# LoraPic2.net
KiCad netlist of a schematic drawn in Altium Designer
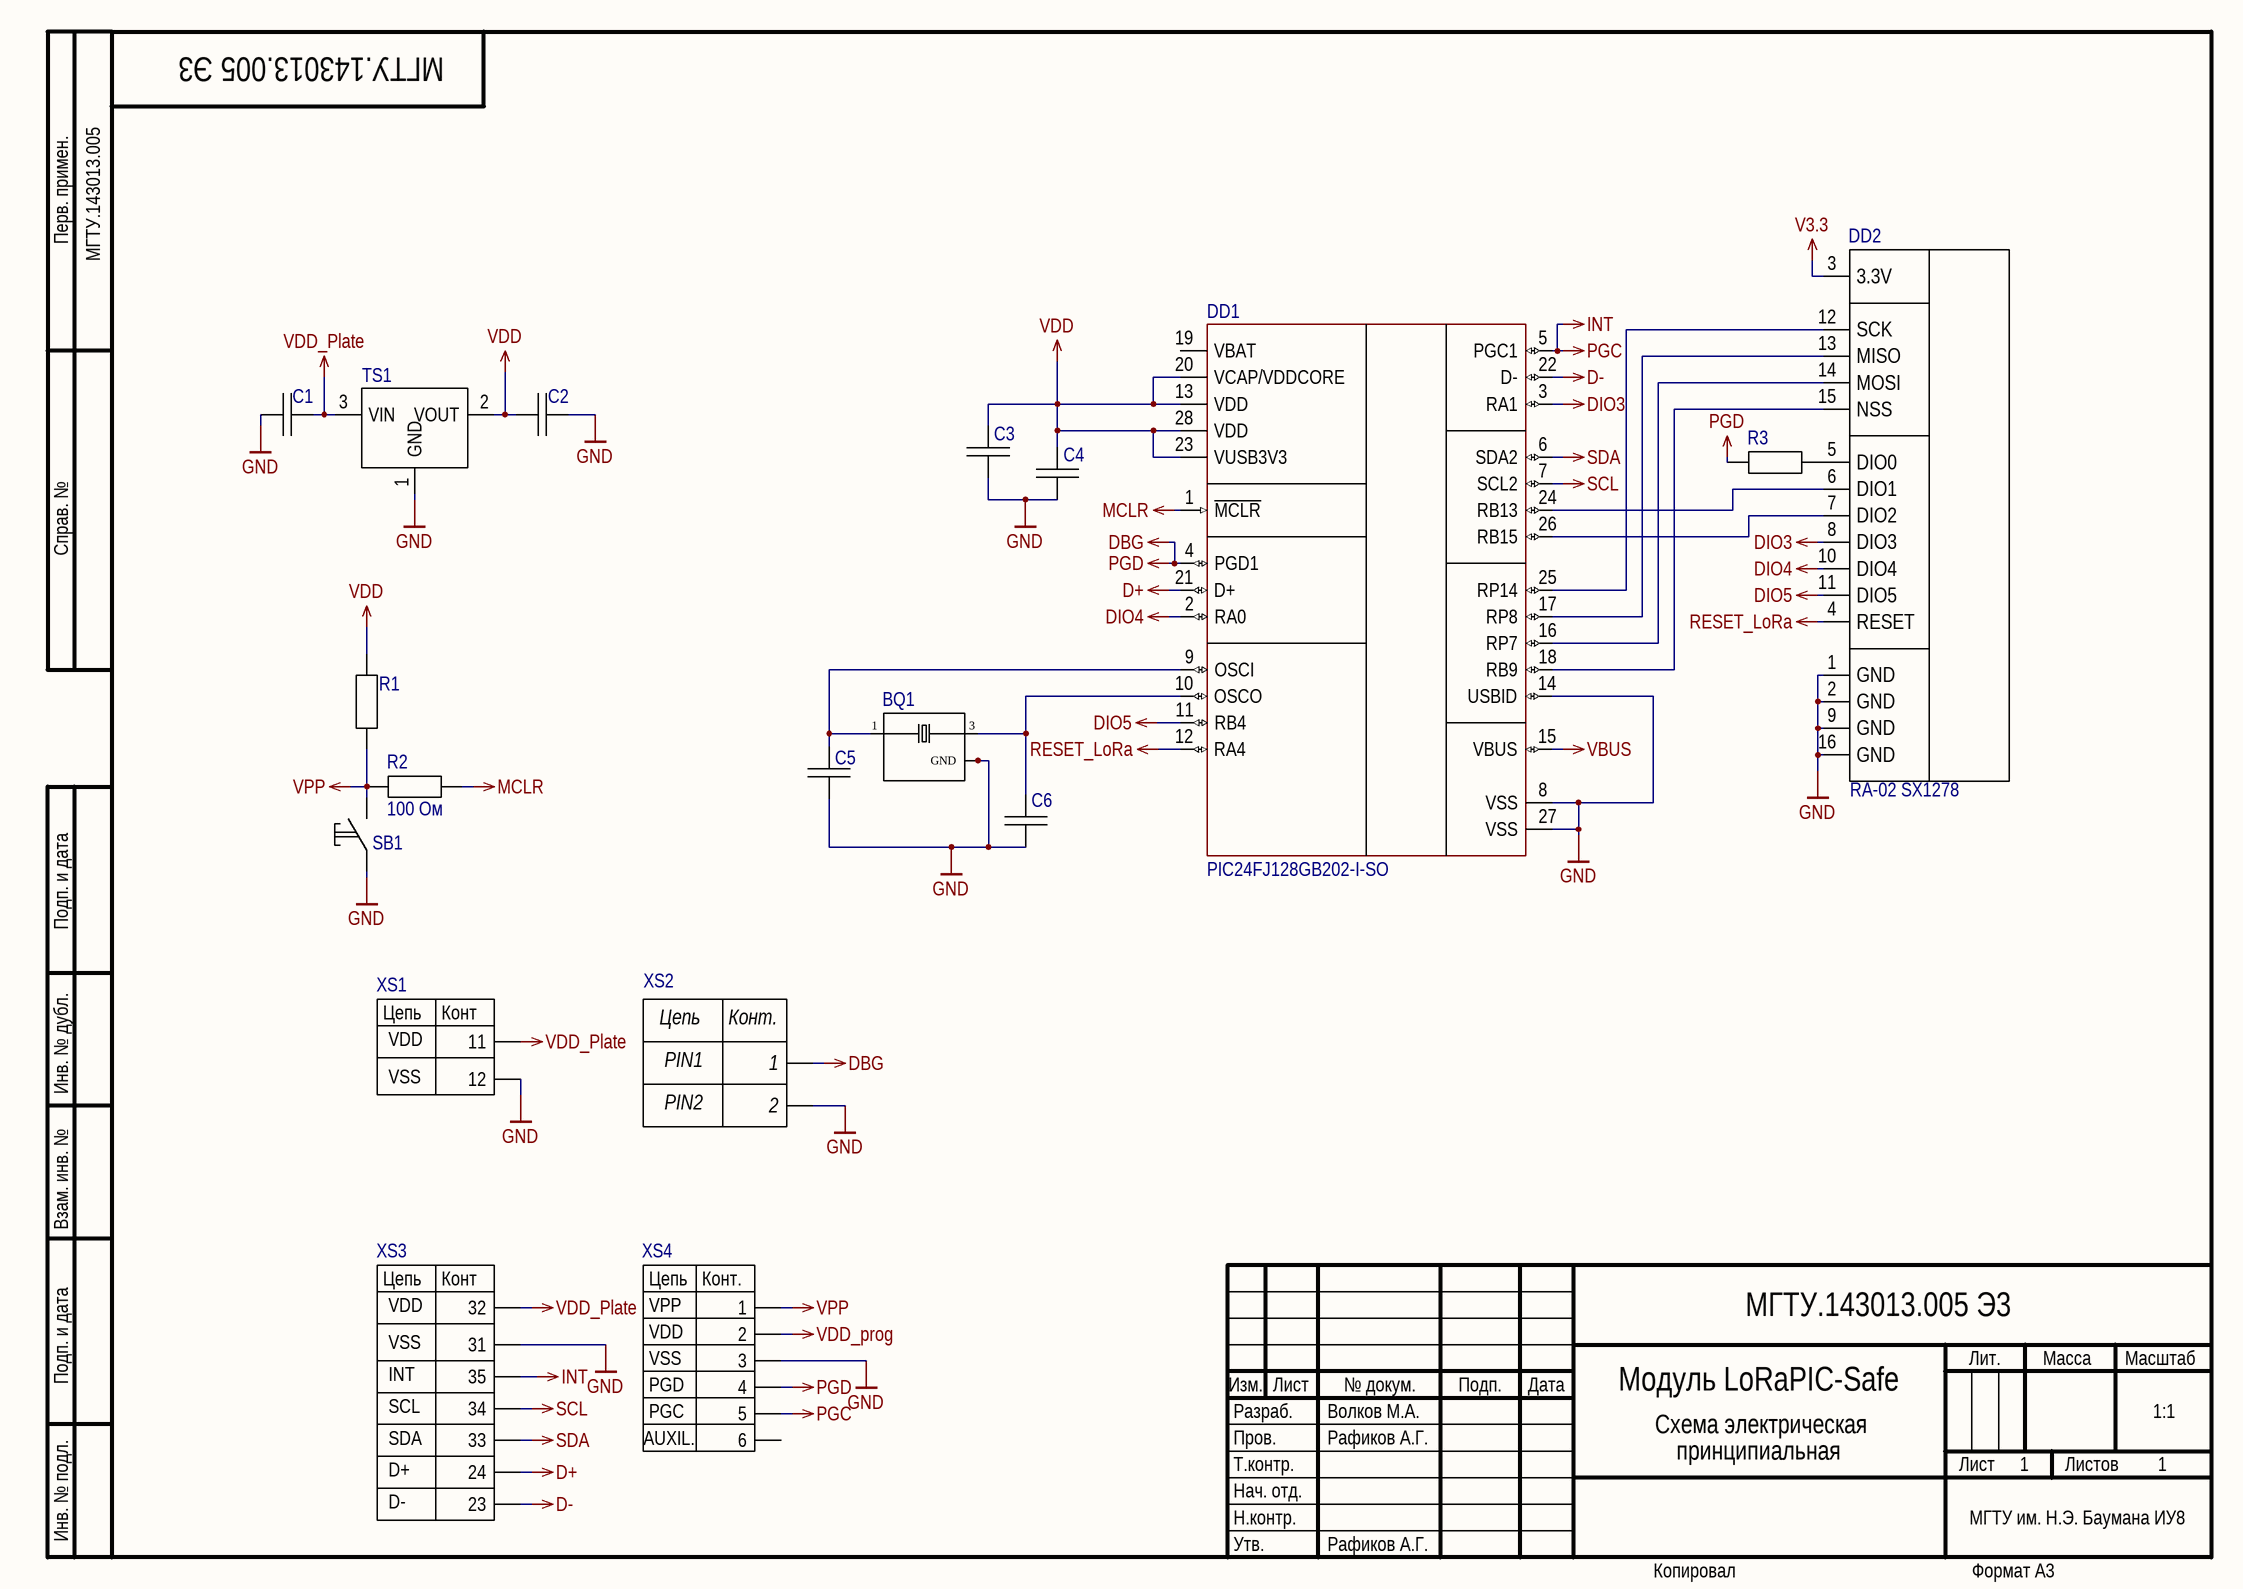
[diagram p0: LoraPic2.SchDoc]

(export (version "E")
  (design (tool "Eeschema 10.0.6"))
  (components
    (comp (ref "BQ1")
      (value "NX2520SA")
      (footprint "*XTAL_NX2520SA-24.000000MHZ-B8")
      (description "CRYSTAL 24.0000MHZ 10PF SMD")
      (fields (field (name "MF") "NDK America, Inc.") (field (name "MP") "NX2520SA-24.000000MHZ-B8"))
      (libsource (lib "godnota") (part "NX2520SA-24.000000MHZ-B8"))
    )
    (comp (ref "C1")
      (value "*")
      (footprint "CAPC1608X09L")
      (description "Конденсатор 1.6x0.8 мм")
      (fields (field (name "TOLERANCE") "±10%"))
      (libsource (lib "RPSLib") (part "CC1608"))
    )
    (comp (ref "C2")
      (value "*")
      (footprint "CAPC1608X09L")
      (description "Конденсатор 1.6x0.8 мм")
      (fields (field (name "TOLERANCE") "±10%"))
      (libsource (lib "RPSLib") (part "CC1608"))
    )
    (comp (ref "C3")
      (value "*")
      (footprint "CAPC1608X09L")
      (description "Конденсатор 1.6x0.8 мм")
      (fields (field (name "TOLERANCE") "±10%"))
      (libsource (lib "RPSLib") (part "CC1608"))
    )
    (comp (ref "C4")
      (value "*")
      (footprint "CAPC1608X09L")
      (description "Конденсатор 1.6x0.8 мм")
      (fields (field (name "TOLERANCE") "±10%"))
      (libsource (lib "RPSLib") (part "CC1608"))
    )
    (comp (ref "C5")
      (value "GRM1885C1H510JA01D")
      (footprint "CAPC1608X09L")
      (description "Конденсатор 1.6x0.8 мм")
      (fields (field (name "TOLERANCE") "±10%"))
      (libsource (lib "RPSLib") (part "CC1608"))
    )
    (comp (ref "C6")
      (value "GRM1885C2A150JA01D")
      (footprint "CAPC1608X09L")
      (description "Конденсатор 0.8x0.5 мм 50 пикофара")
      (fields (field (name "TOLERANCE") "±10%"))
      (libsource (lib "RPSLib") (part "CC1608"))
    )
    (comp (ref "DD1")
      (value "PIC24FJ128GB202-I-SO")
      (footprint "Microchip_SO-28_0")
      (libsource (lib "IC_Microchip_PIC24FJ128GB202-I-SO_eec") (part "PIC24FJ128GB202-I-SO"))
    )
    (comp (ref "DD2") (value "RA-02 SX1278") (footprint "RA-02") (libsource (lib "RA-02") (part "RA-02")))
    (comp (ref "R1")
      (value "RC0603FR-0710KL")
      (footprint "RESC1608X05N")
      (description "Резистор 1.6x0.8 мм")
      (fields (field (name "TOLERANCE") "±5%"))
      (libsource (lib "RPSLib") (part "R1608"))
    )
    (comp (ref "R2")
      (value "100 Ом")
      (footprint "RESC1608X05N")
      (description "Резистор 1.6x0.8 мм")
      (fields (field (name "TOLERANCE") "±5%") (field (name "Comment") "100 ом до 470"))
      (libsource (lib "RPSLib") (part "R1608"))
    )
    (comp (ref "R3")
      (value "100 ом до 470")
      (footprint "RESC1608X05N")
      (description "Резистор 1.6x0.8 мм")
      (fields (field (name "TOLERANCE") "±5%"))
      (libsource (lib "RPSLib") (part "R1608"))
    )
    (comp (ref "SB1")
      (value "1437566-3 (FSMSM)")
      (footprint "*SW_1437566-4")
      (libsource (lib "godnota") (part "FSMSM"))
    )
    (comp (ref "TS1")
      (value "LD1117S33CTR")
      (footprint "*SOT223")
      (description "Linear Regulator\r\nLDO Regulator Pos 3.3V 1.3A 4-Pin(3+Tab) SOT-223 T/R")
      (libsource (lib "godnota") (part "LD1117S33CTR"))
    )
    (comp (ref "XS1") (value "PBS-20") (footprint "PBS-20 - 13") (libsource (lib "RPSLib") (part "PBS-20_1")))
    (comp (ref "XS2")
      (value "DS1066-02M(MW-2M)")
      (footprint "B2B-XH-A")
      (description "Разъем 2")
      (fields
        (field (name "MANUFACTURER") "JST")
        (field (name "MANUFACTURER PART NUMBER") "B2B-XH-A(LF)(SN)")
      )
      (libsource (lib "RPSLib") (part "B2B-XH-A"))
    )
    (comp (ref "XS3") (value "PBS-20") (footprint "PBS-20") (libsource (lib "RPSLib") (part "PBS_20_2")))
    (comp (ref "XS4")
      (value "DS1021-2x3S")
      (footprint "DS1021-2x3S")
      (libsource (lib "RPSLib") (part "PLD3X2"))
    )
  )
  (nets
    (net (code "1") (name "D+") (class "Default")
      (node (ref "DD1") (pin "21") (pinfunction "D+_21") (pintype "bidirectional"))
      (node (ref "XS3") (pin "17") (pinfunction "24_17") (pintype "passive"))
    )
    (net (code "2") (name "D-") (class "Default")
      (node (ref "DD1") (pin "22") (pinfunction "D-_22") (pintype "bidirectional"))
      (node (ref "XS3") (pin "18") (pinfunction "23_18") (pintype "passive"))
    )
    (net (code "3") (name "DBG") (class "Default")
      (node (ref "DD1") (pin "4") (pinfunction "PGD1_4") (pintype "bidirectional"))
      (node (ref "R3") (pin "2") (pinfunction "2_2") (pintype "passive"))
      (node (ref "XS2") (pin "1") (pinfunction "1_1") (pintype "passive"))
      (node (ref "XS4") (pin "4") (pinfunction "4_4") (pintype "passive"))
    )
    (net (code "4") (name "DIO3") (class "Default")
      (node (ref "DD1") (pin "3") (pinfunction "RA1_3") (pintype "bidirectional"))
      (node (ref "DD2") (pin "8") (pinfunction "DIO3_8") (pintype "passive"))
    )
    (net (code "5") (name "DIO4") (class "Default")
      (node (ref "DD1") (pin "2") (pinfunction "RA0_2") (pintype "bidirectional"))
      (node (ref "DD2") (pin "10") (pinfunction "DIO4_10") (pintype "passive"))
    )
    (net (code "6") (name "DIO5") (class "Default")
      (node (ref "DD1") (pin "11") (pinfunction "RB4_11") (pintype "bidirectional"))
      (node (ref "DD2") (pin "11") (pinfunction "DIO5_11") (pintype "passive"))
    )
    (net (code "7") (name "GND") (class "Default")
      (node (ref "BQ1") (pin "2") (pinfunction "GND_2") (pintype "power_in"))
      (node (ref "BQ1") (pin "4") (pinfunction "GND_4") (pintype "power_in"))
      (node (ref "C1") (pin "2") (pinfunction "2_2") (pintype "passive"))
      (node (ref "C2") (pin "1") (pinfunction "1_1") (pintype "passive"))
      (node (ref "C3") (pin "2") (pinfunction "2_2") (pintype "passive"))
      (node (ref "C4") (pin "2") (pinfunction "2_2") (pintype "passive"))
      (node (ref "C5") (pin "2") (pinfunction "2_2") (pintype "passive"))
      (node (ref "C6") (pin "2") (pinfunction "2_2") (pintype "passive"))
      (node (ref "DD1") (pin "14") (pinfunction "USBID_14") (pintype "bidirectional"))
      (node (ref "DD1") (pin "27") (pinfunction "VSS_27") (pintype "power_in"))
      (node (ref "DD1") (pin "8") (pinfunction "VSS_8") (pintype "power_in"))
      (node (ref "DD2") (pin "1") (pinfunction "GND_1") (pintype "passive"))
      (node (ref "DD2") (pin "16") (pinfunction "GND_16") (pintype "passive"))
      (node (ref "DD2") (pin "2") (pinfunction "GND_2") (pintype "passive"))
      (node (ref "DD2") (pin "9") (pinfunction "GND_9") (pintype "passive"))
      (node (ref "SB1") (pin "1") (pinfunction "1_1") (pintype "passive"))
      (node (ref "TS1") (pin "1") (pinfunction "GND_1") (pintype "power_in"))
      (node (ref "XS1") (pin "12") (pinfunction "12_12") (pintype "passive"))
      (node (ref "XS2") (pin "2") (pinfunction "2_2") (pintype "passive"))
      (node (ref "XS3") (pin "10") (pinfunction "31_10") (pintype "passive"))
      (node (ref "XS4") (pin "3") (pinfunction "3_3") (pintype "passive"))
    )
    (net (code "8") (name "INT") (class "Default")
      (node (ref "DD1") (pin "5") (pinfunction "PGC1_5") (pintype "bidirectional"))
      (node (ref "XS3") (pin "6") (pinfunction "35_6") (pintype "passive"))
      (node (ref "XS4") (pin "5") (pinfunction "5_5") (pintype "passive"))
    )
    (net (code "9") (name "MCLR") (class "Default")
      (node (ref "DD1") (pin "1") (pinfunction "~{MCLR}_1") (pintype "input"))
      (node (ref "R2") (pin "1") (pinfunction "1_1") (pintype "passive"))
    )
    (net (code "10") (name "Net-(DD1-OSCI)") (class "Default")
      (node (ref "BQ1") (pin "1") (pinfunction "1_1") (pintype "passive"))
      (node (ref "C5") (pin "1") (pinfunction "1_1") (pintype "passive"))
      (node (ref "DD1") (pin "9") (pinfunction "OSCI_9") (pintype "bidirectional"))
    )
    (net (code "11") (name "Net-(DD1-OSCO)") (class "Default")
      (node (ref "BQ1") (pin "3") (pinfunction "3_3") (pintype "passive"))
      (node (ref "C6") (pin "1") (pinfunction "1_1") (pintype "passive"))
      (node (ref "DD1") (pin "10") (pinfunction "OSCO_10") (pintype "bidirectional"))
    )
    (net (code "12") (name "Net-(DD1-RB9)") (class "Default")
      (node (ref "DD1") (pin "18") (pinfunction "RB9_18") (pintype "bidirectional"))
      (node (ref "DD2") (pin "15") (pinfunction "NSS_15") (pintype "passive"))
    )
    (net (code "13") (name "Net-(DD1-RB13)") (class "Default")
      (node (ref "DD1") (pin "24") (pinfunction "RB13_24") (pintype "bidirectional"))
      (node (ref "DD2") (pin "6") (pinfunction "DIO1_6") (pintype "passive"))
    )
    (net (code "14") (name "Net-(DD1-RB15)") (class "Default")
      (node (ref "DD1") (pin "26") (pinfunction "RB15_26") (pintype "bidirectional"))
      (node (ref "DD2") (pin "7") (pinfunction "DIO2_7") (pintype "passive"))
    )
    (net (code "15") (name "Net-(DD1-RP7)") (class "Default")
      (node (ref "DD1") (pin "16") (pinfunction "RP7_16") (pintype "bidirectional"))
      (node (ref "DD2") (pin "14") (pinfunction "MOSI_14") (pintype "passive"))
    )
    (net (code "16") (name "Net-(DD1-RP8)") (class "Default")
      (node (ref "DD1") (pin "17") (pinfunction "RP8_17") (pintype "bidirectional"))
      (node (ref "DD2") (pin "13") (pinfunction "MISO_13") (pintype "passive"))
    )
    (net (code "17") (name "Net-(DD1-RP14)") (class "Default")
      (node (ref "DD1") (pin "25") (pinfunction "RP14_25") (pintype "bidirectional"))
      (node (ref "DD2") (pin "12") (pinfunction "SCK_12") (pintype "passive"))
    )
    (net (code "18") (name "Net-(DD2-DIO0)") (class "Default")
      (node (ref "DD2") (pin "5") (pinfunction "DIO0_5") (pintype "passive"))
      (node (ref "R3") (pin "1") (pinfunction "1_1") (pintype "passive"))
    )
    (net (code "19") (name "RESET_LoRa") (class "Default")
      (node (ref "DD1") (pin "12") (pinfunction "RA4_12") (pintype "bidirectional"))
      (node (ref "DD2") (pin "4") (pinfunction "RESET_4") (pintype "passive"))
    )
    (net (code "20") (name "SCL") (class "Default")
      (node (ref "DD1") (pin "7") (pinfunction "SCL2_7") (pintype "bidirectional"))
      (node (ref "XS3") (pin "7") (pinfunction "34_7") (pintype "passive"))
    )
    (net (code "21") (name "SDA") (class "Default")
      (node (ref "DD1") (pin "6") (pinfunction "SDA2_6") (pintype "bidirectional"))
      (node (ref "XS3") (pin "8") (pinfunction "33_8") (pintype "passive"))
    )
    (net (code "22") (name "V3.3") (class "Default")
      (node (ref "DD2") (pin "3") (pinfunction "3.3V_3") (pintype "passive"))
    )
    (net (code "23") (name "VBUS") (class "Default")
      (node (ref "DD1") (pin "15") (pinfunction "VBUS_15") (pintype "bidirectional"))
    )
    (net (code "24") (name "VDD") (class "Default")
      (node (ref "C2") (pin "2") (pinfunction "2_2") (pintype "passive"))
      (node (ref "C3") (pin "1") (pinfunction "1_1") (pintype "passive"))
      (node (ref "C4") (pin "1") (pinfunction "1_1") (pintype "passive"))
      (node (ref "DD1") (pin "13") (pinfunction "VDD_13") (pintype "power_in"))
      (node (ref "DD1") (pin "20") (pinfunction "VCAP/VDDCORE_20") (pintype "power_in"))
      (node (ref "DD1") (pin "23") (pinfunction "VUSB3V3_23") (pintype "power_in"))
      (node (ref "DD1") (pin "28") (pinfunction "VDD_28") (pintype "power_in"))
      (node (ref "R1") (pin "1") (pinfunction "1_1") (pintype "passive"))
      (node (ref "TS1") (pin "2") (pinfunction "VOUT_2") (pintype "power_in"))
    )
    (net (code "25") (name "VDD_Plate") (class "Default")
      (node (ref "C1") (pin "1") (pinfunction "1_1") (pintype "passive"))
      (node (ref "TS1") (pin "3") (pinfunction "VIN_3") (pintype "power_in"))
      (node (ref "XS1") (pin "11") (pinfunction "11_11") (pintype "passive"))
      (node (ref "XS3") (pin "9") (pinfunction "32_9") (pintype "passive"))
    )
    (net (code "26") (name "VDD_prog") (class "Default")
      (node (ref "XS4") (pin "2") (pinfunction "2_2") (pintype "passive"))
    )
    (net (code "27") (name "VPP") (class "Default")
      (node (ref "R1") (pin "2") (pinfunction "2_2") (pintype "passive"))
      (node (ref "R2") (pin "2") (pinfunction "2_2") (pintype "passive"))
      (node (ref "SB1") (pin "2") (pinfunction "2_2") (pintype "passive"))
      (node (ref "XS4") (pin "1") (pinfunction "1_1") (pintype "passive"))
    )
    (net (code "28") (name "unconnected-(DD1-VBAT-Pad19)") (class "Default")
      (node (ref "DD1") (pin "19") (pinfunction "VBAT_19") (pintype "power_in"))
    )
    (net (code "29") (name "unconnected-(XS4-Pad6)") (class "Default")
      (node (ref "XS4") (pin "6") (pinfunction "6_6") (pintype "passive"))
    )
  )
)
